# Sheet1.net
KiCad netlist of a schematic drawn in Altium Designer
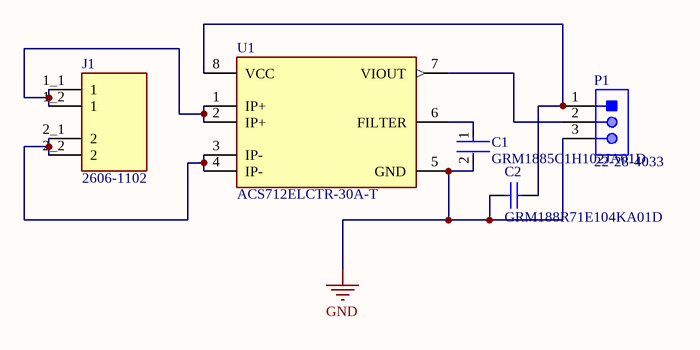
[diagram p0: Sheet1.SchDoc]

(export (version "E")
  (design (tool "Eeschema 10.0.6"))
  (components
    (comp (ref "C1")
      (value "GRM1885C1H102JA01D")
      (footprint "FP-GRM188-0_1-e0_2_0_5-IPC_C")
      (description "Chip Multilayer Ceramic Capacitors for General Purpose, 0603, 1000pF, C0G, 30ppm/°C, 5%, 50V")
      (fields (field (name "TOLERANCE") "5%") (field (name "VOLTAGE") "50V"))
      (libsource (lib "Altium Content Vault") (part "11868f565c42a9108669ba33697ecf6"))
    )
    (comp (ref "C2")
      (value "GRM188R71E104KA01D")
      (footprint "CAPC1608X90X35LL10T15")
      (fields (field (name "MANUFACTURER") "Murata"))
      (libsource (lib "Altium Content Vault") (part "CAP"))
    )
    (comp (ref "J1")
      (value "2606-1102")
      (footprint "WAGO_2606-1102")
      (description "2 Position Wire to Board Terminal Block Horizontal with Board 0.295 (7.50mm) Through Hole")
      (fields (field (name "MF") "WAGO"))
      (libsource (lib "2606-1102") (part "2606-1102"))
    )
    (comp (ref "P1")
      (value "22-28-4033")
      (footprint "MOLX-22-28-4033_V")
      (description "Male Header, Pitch 2.54 mm, 1 x 3 Position, Height 8.38 mm, Tail Length 3.18 mm, RoHS, Bulk")
      (fields (field (name "MANUFACTURER") "Molex"))
      (libsource (lib "Altium Content Vault") (part "CN-1P-M-R3"))
    )
    (comp (ref "U1")
      (value "ACS712ELCTR-30A-T")
      (footprint "FP-LC-8-IPC_C")
      (description "SENSOR CURRENT HALL 30A AC/DC")
      (libsource (lib "Altium Content Vault") (part "a0faa98973ef06dd62ff869f1199b2d"))
    )
  )
  (nets
    (net (code "1") (name "GND") (class "Default")
      (node (ref "C1") (pin "2") (pinfunction "2_2") (pintype "passive"))
      (node (ref "C2") (pin "1") (pinfunction "1_1") (pintype "passive"))
      (node (ref "P1") (pin "3") (pinfunction "3_3") (pintype "passive"))
      (node (ref "U1") (pin "5") (pinfunction "GND_5") (pintype "power_in"))
    )
    (net (code "2") (name "Net-(J1-1-Pad1_1)") (class "Default")
      (node (ref "J1") (pin "1_1") (pinfunction "1_1_1") (pintype "passive"))
      (node (ref "J1") (pin "1_2") (pinfunction "1_1_2") (pintype "passive"))
      (node (ref "U1") (pin "1") (pinfunction "IP+_1") (pintype "passive"))
      (node (ref "U1") (pin "2") (pinfunction "IP+_2") (pintype "passive"))
    )
    (net (code "3") (name "Net-(J1-2-Pad2_1)") (class "Default")
      (node (ref "J1") (pin "2_1") (pinfunction "2_2_1") (pintype "passive"))
      (node (ref "J1") (pin "2_2") (pinfunction "2_2_2") (pintype "passive"))
      (node (ref "U1") (pin "3") (pinfunction "IP-_3") (pintype "passive"))
      (node (ref "U1") (pin "4") (pinfunction "IP-_4") (pintype "passive"))
    )
    (net (code "4") (name "Net-(U1-FILTER)") (class "Default")
      (node (ref "C1") (pin "1") (pinfunction "1_1") (pintype "passive"))
      (node (ref "U1") (pin "6") (pinfunction "FILTER_6") (pintype "passive"))
    )
    (net (code "5") (name "Net-(U1-VCC)") (class "Default")
      (node (ref "C2") (pin "2") (pinfunction "2_2") (pintype "passive"))
      (node (ref "P1") (pin "1") (pinfunction "1_1") (pintype "passive"))
      (node (ref "U1") (pin "8") (pinfunction "VCC_8") (pintype "power_in"))
    )
    (net (code "6") (name "Net-(U1-VIOUT)") (class "Default")
      (node (ref "P1") (pin "2") (pinfunction "2_2") (pintype "passive"))
      (node (ref "U1") (pin "7") (pinfunction "VIOUT_7") (pintype "output"))
    )
  )
)
